# SplitterBoxRevC.net
KiCad netlist of a schematic drawn in EAGLE
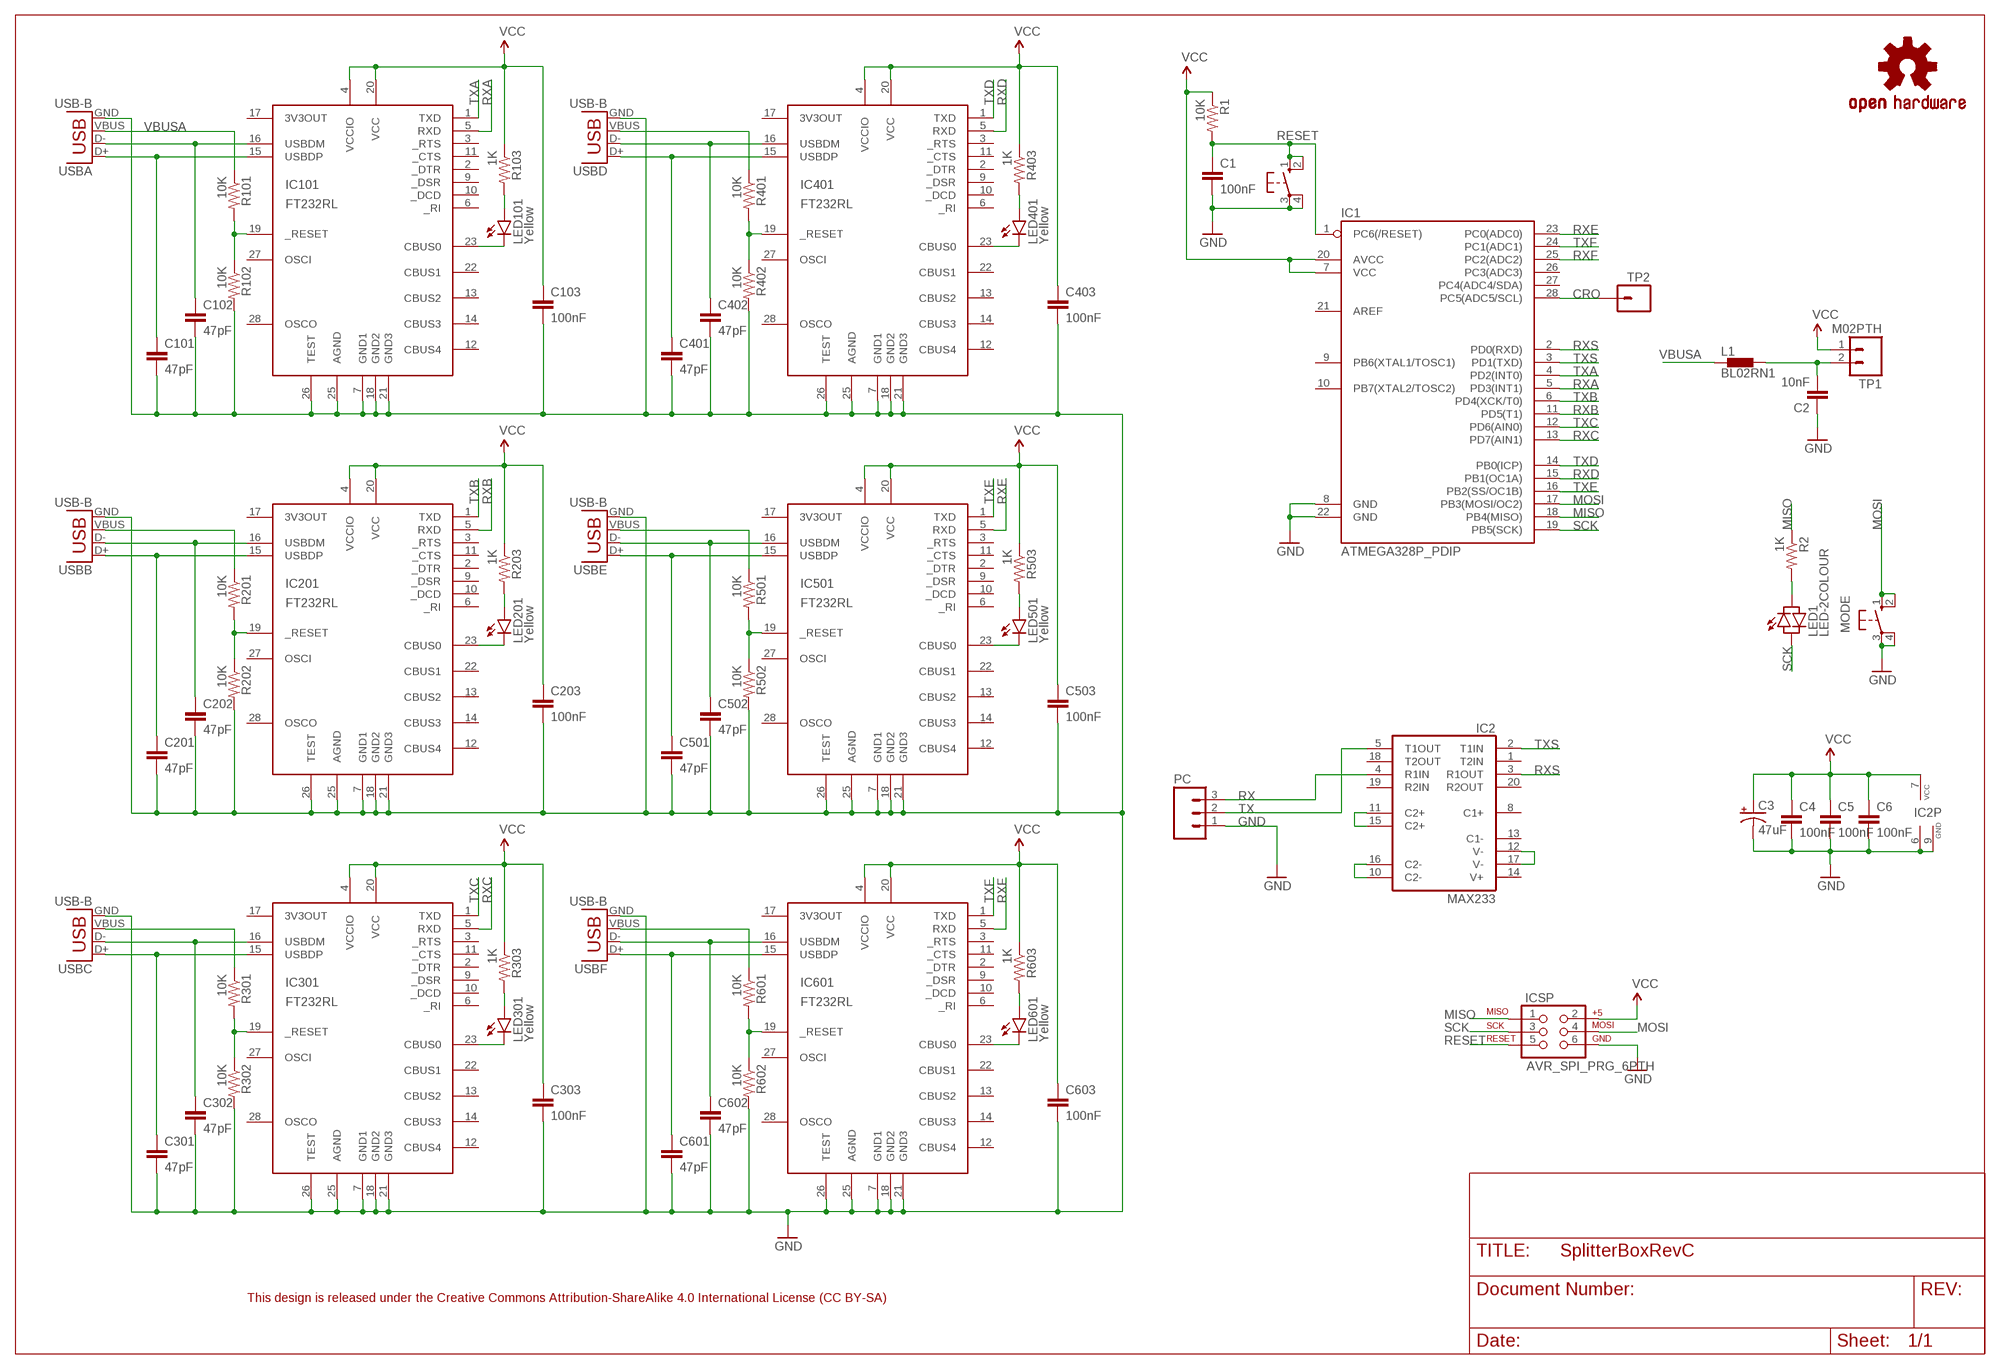
[diagram p0: schematic, sheet 1]

(export (version "E")
  (design (tool "Eeschema 10.0.6"))
  (components
    (comp (ref "C1")
      (value "100nF")
      (footprint "eagle-import:CAP-PTH-SMALL")
      (libsource (lib "eagle-import") (part "CAPPTH"))
    )
    (comp (ref "C2")
      (value "10nF")
      (footprint "eagle-import:CAP-PTH-SMALL")
      (libsource (lib "eagle-import") (part "CAPPTH"))
    )
    (comp (ref "C3")
      (value "47uF")
      (footprint "eagle-import:CPOL-RADIAL-100UF-25V")
      (libsource (lib "eagle-import") (part "CAP_POLPTH1"))
    )
    (comp (ref "C4")
      (value "100nF")
      (footprint "eagle-import:CAP-PTH-SMALL")
      (libsource (lib "eagle-import") (part "CAPPTH"))
    )
    (comp (ref "C5")
      (value "100nF")
      (footprint "eagle-import:CAP-PTH-SMALL")
      (libsource (lib "eagle-import") (part "CAPPTH"))
    )
    (comp (ref "C6")
      (value "100nF")
      (footprint "eagle-import:CAP-PTH-SMALL")
      (libsource (lib "eagle-import") (part "CAPPTH"))
    )
    (comp (ref "C101")
      (value "47pF")
      (footprint "eagle-import:CAP-PTH-SMALL")
      (libsource (lib "eagle-import") (part "CAPPTH"))
    )
    (comp (ref "C102")
      (value "47pF")
      (footprint "eagle-import:CAP-PTH-SMALL")
      (libsource (lib "eagle-import") (part "CAPPTH"))
    )
    (comp (ref "C103")
      (value "100nF")
      (footprint "eagle-import:CAP-PTH-SMALL")
      (libsource (lib "eagle-import") (part "CAPPTH"))
    )
    (comp (ref "C201")
      (value "47pF")
      (footprint "eagle-import:CAP-PTH-SMALL")
      (libsource (lib "eagle-import") (part "CAPPTH"))
    )
    (comp (ref "C202")
      (value "47pF")
      (footprint "eagle-import:CAP-PTH-SMALL")
      (libsource (lib "eagle-import") (part "CAPPTH"))
    )
    (comp (ref "C203")
      (value "100nF")
      (footprint "eagle-import:CAP-PTH-SMALL")
      (libsource (lib "eagle-import") (part "CAPPTH"))
    )
    (comp (ref "C301")
      (value "47pF")
      (footprint "eagle-import:CAP-PTH-SMALL")
      (libsource (lib "eagle-import") (part "CAPPTH"))
    )
    (comp (ref "C302")
      (value "47pF")
      (footprint "eagle-import:CAP-PTH-SMALL")
      (libsource (lib "eagle-import") (part "CAPPTH"))
    )
    (comp (ref "C303")
      (value "100nF")
      (footprint "eagle-import:CAP-PTH-SMALL")
      (libsource (lib "eagle-import") (part "CAPPTH"))
    )
    (comp (ref "C401")
      (value "47pF")
      (footprint "eagle-import:CAP-PTH-SMALL")
      (libsource (lib "eagle-import") (part "CAPPTH"))
    )
    (comp (ref "C402")
      (value "47pF")
      (footprint "eagle-import:CAP-PTH-SMALL")
      (libsource (lib "eagle-import") (part "CAPPTH"))
    )
    (comp (ref "C403")
      (value "100nF")
      (footprint "eagle-import:CAP-PTH-SMALL")
      (libsource (lib "eagle-import") (part "CAPPTH"))
    )
    (comp (ref "C501")
      (value "47pF")
      (footprint "eagle-import:CAP-PTH-SMALL")
      (libsource (lib "eagle-import") (part "CAPPTH"))
    )
    (comp (ref "C502")
      (value "47pF")
      (footprint "eagle-import:CAP-PTH-SMALL")
      (libsource (lib "eagle-import") (part "CAPPTH"))
    )
    (comp (ref "C503")
      (value "100nF")
      (footprint "eagle-import:CAP-PTH-SMALL")
      (libsource (lib "eagle-import") (part "CAPPTH"))
    )
    (comp (ref "C601")
      (value "47pF")
      (footprint "eagle-import:CAP-PTH-SMALL")
      (libsource (lib "eagle-import") (part "CAPPTH"))
    )
    (comp (ref "C602")
      (value "47pF")
      (footprint "eagle-import:CAP-PTH-SMALL")
      (libsource (lib "eagle-import") (part "CAPPTH"))
    )
    (comp (ref "C603")
      (value "100nF")
      (footprint "eagle-import:CAP-PTH-SMALL")
      (libsource (lib "eagle-import") (part "CAPPTH"))
    )
    (comp (ref "IC1")
      (value "ATMEGA328P_PDIP")
      (footprint "eagle-import:DIL28-3")
      (libsource (lib "eagle-import") (part "ATMEGA328P_PDIP"))
    )
    (comp (ref "IC2")
      (value "MAX233")
      (footprint "eagle-import:DIL20")
      (fields (field (name "MPN") "MAX233ACPP+G36"))
      (libsource (lib "eagle-import") (part "MAX233"))
    )
    (comp (ref "IC101")
      (value "FT232RL")
      (footprint "eagle-import:SSOP28DB")
      (libsource (lib "eagle-import") (part "FT232RL"))
    )
    (comp (ref "IC201")
      (value "FT232RL")
      (footprint "eagle-import:SSOP28DB")
      (libsource (lib "eagle-import") (part "FT232RL"))
    )
    (comp (ref "IC301")
      (value "FT232RL")
      (footprint "eagle-import:SSOP28DB")
      (libsource (lib "eagle-import") (part "FT232RL"))
    )
    (comp (ref "IC401")
      (value "FT232RL")
      (footprint "eagle-import:SSOP28DB")
      (libsource (lib "eagle-import") (part "FT232RL"))
    )
    (comp (ref "IC501")
      (value "FT232RL")
      (footprint "eagle-import:SSOP28DB")
      (libsource (lib "eagle-import") (part "FT232RL"))
    )
    (comp (ref "IC601")
      (value "FT232RL")
      (footprint "eagle-import:SSOP28DB")
      (libsource (lib "eagle-import") (part "FT232RL"))
    )
    (comp (ref "ICSP")
      (value "AVR_SPI_PRG_6PTH")
      (footprint "eagle-import:2X3")
      (libsource (lib "eagle-import") (part "AVR_SPI_PRG_6PTH"))
    )
    (comp (ref "L1")
      (value "BL02RN1")
      (footprint "eagle-import:BL02RN1")
      (libsource (lib "eagle-import") (part "BL02RN1"))
    )
    (comp (ref "LED1")
      (value "LED-2COLOUR")
      (footprint "eagle-import:LED3MM")
      (libsource (lib "eagle-import") (part "LED-2COLOUR"))
    )
    (comp (ref "LED101")
      (value "Yellow")
      (footprint "eagle-import:LED3MM_LARGEHOLES")
      (libsource (lib "eagle-import") (part "LED-LH3MM"))
    )
    (comp (ref "LED201")
      (value "Yellow")
      (footprint "eagle-import:LED3MM_LARGEHOLES")
      (libsource (lib "eagle-import") (part "LED-LH3MM"))
    )
    (comp (ref "LED301")
      (value "Yellow")
      (footprint "eagle-import:LED3MM_LARGEHOLES")
      (libsource (lib "eagle-import") (part "LED-LH3MM"))
    )
    (comp (ref "LED401")
      (value "Yellow")
      (footprint "eagle-import:LED3MM_LARGEHOLES")
      (libsource (lib "eagle-import") (part "LED-LH3MM"))
    )
    (comp (ref "LED501")
      (value "Yellow")
      (footprint "eagle-import:LED3MM_LARGEHOLES")
      (libsource (lib "eagle-import") (part "LED-LH3MM"))
    )
    (comp (ref "LED601")
      (value "Yellow")
      (footprint "eagle-import:LED3MM_LARGEHOLES")
      (libsource (lib "eagle-import") (part "LED-LH3MM"))
    )
    (comp (ref "LOGO1")
      (value "OSHW-LOGOS")
      (footprint "eagle-import:OSHW-LOGO-S")
      (libsource (lib "eagle-import") (part "OSHW-LOGOS"))
    )
    (comp (ref "MODE")
      (value "10-XX")
      (footprint "eagle-import:B3F-10XX")
      (fields (field (name "MPN") "B3F-1000"))
      (libsource (lib "eagle-import") (part "10-XX"))
    )
    (comp (ref "PC")
      (value "M03PTH")
      (footprint "eagle-import:1X03")
      (libsource (lib "eagle-import") (part "M03PTH"))
    )
    (comp (ref "R1")
      (value "10K")
      (footprint "eagle-import:AXIAL-0.4")
      (libsource (lib "eagle-import") (part "RESISTORPTH-1/4W"))
    )
    (comp (ref "R2")
      (value "1K")
      (footprint "eagle-import:AXIAL-0.4")
      (libsource (lib "eagle-import") (part "RESISTORPTH-1/4W"))
    )
    (comp (ref "R101")
      (value "10K")
      (footprint "eagle-import:AXIAL-0.4")
      (libsource (lib "eagle-import") (part "RESISTORPTH-1/4W"))
    )
    (comp (ref "R102")
      (value "10K")
      (footprint "eagle-import:AXIAL-0.4")
      (libsource (lib "eagle-import") (part "RESISTORPTH-1/4W"))
    )
    (comp (ref "R103")
      (value "1K")
      (footprint "eagle-import:AXIAL-0.4")
      (libsource (lib "eagle-import") (part "RESISTORPTH-1/4W"))
    )
    (comp (ref "R201")
      (value "10K")
      (footprint "eagle-import:AXIAL-0.4")
      (libsource (lib "eagle-import") (part "RESISTORPTH-1/4W"))
    )
    (comp (ref "R202")
      (value "10K")
      (footprint "eagle-import:AXIAL-0.4")
      (libsource (lib "eagle-import") (part "RESISTORPTH-1/4W"))
    )
    (comp (ref "R203")
      (value "1K")
      (footprint "eagle-import:AXIAL-0.4")
      (libsource (lib "eagle-import") (part "RESISTORPTH-1/4W"))
    )
    (comp (ref "R301")
      (value "10K")
      (footprint "eagle-import:AXIAL-0.4")
      (libsource (lib "eagle-import") (part "RESISTORPTH-1/4W"))
    )
    (comp (ref "R302")
      (value "10K")
      (footprint "eagle-import:AXIAL-0.4")
      (libsource (lib "eagle-import") (part "RESISTORPTH-1/4W"))
    )
    (comp (ref "R303")
      (value "1K")
      (footprint "eagle-import:AXIAL-0.4")
      (libsource (lib "eagle-import") (part "RESISTORPTH-1/4W"))
    )
    (comp (ref "R401")
      (value "10K")
      (footprint "eagle-import:AXIAL-0.4")
      (libsource (lib "eagle-import") (part "RESISTORPTH-1/4W"))
    )
    (comp (ref "R402")
      (value "10K")
      (footprint "eagle-import:AXIAL-0.4")
      (libsource (lib "eagle-import") (part "RESISTORPTH-1/4W"))
    )
    (comp (ref "R403")
      (value "1K")
      (footprint "eagle-import:AXIAL-0.4")
      (libsource (lib "eagle-import") (part "RESISTORPTH-1/4W"))
    )
    (comp (ref "R501")
      (value "10K")
      (footprint "eagle-import:AXIAL-0.4")
      (libsource (lib "eagle-import") (part "RESISTORPTH-1/4W"))
    )
    (comp (ref "R502")
      (value "10K")
      (footprint "eagle-import:AXIAL-0.4")
      (libsource (lib "eagle-import") (part "RESISTORPTH-1/4W"))
    )
    (comp (ref "R503")
      (value "1K")
      (footprint "eagle-import:AXIAL-0.4")
      (libsource (lib "eagle-import") (part "RESISTORPTH-1/4W"))
    )
    (comp (ref "R601")
      (value "10K")
      (footprint "eagle-import:AXIAL-0.4")
      (libsource (lib "eagle-import") (part "RESISTORPTH-1/4W"))
    )
    (comp (ref "R602")
      (value "10K")
      (footprint "eagle-import:AXIAL-0.4")
      (libsource (lib "eagle-import") (part "RESISTORPTH-1/4W"))
    )
    (comp (ref "R603")
      (value "1K")
      (footprint "eagle-import:AXIAL-0.4")
      (libsource (lib "eagle-import") (part "RESISTORPTH-1/4W"))
    )
    (comp (ref "RST")
      (value "10-XX")
      (footprint "eagle-import:B3F-10XX")
      (fields (field (name "MPN") "B3F-1000"))
      (libsource (lib "eagle-import") (part "10-XX"))
    )
    (comp (ref "TP1")
      (value "M02PTH")
      (footprint "eagle-import:1X02")
      (libsource (lib "eagle-import") (part "M02PTH"))
    )
    (comp (ref "TP2")
      (value "M01PTH")
      (footprint "eagle-import:1X01")
      (libsource (lib "eagle-import") (part "M01PTH"))
    )
    (comp (ref "USBA")
      (value "USB-B")
      (footprint "eagle-import:USB-B-PTH")
      (libsource (lib "eagle-import") (part "USBPTH"))
    )
    (comp (ref "USBB")
      (value "USB-B")
      (footprint "eagle-import:USB-B-PTH")
      (libsource (lib "eagle-import") (part "USBPTH"))
    )
    (comp (ref "USBC")
      (value "USB-B")
      (footprint "eagle-import:USB-B-PTH")
      (libsource (lib "eagle-import") (part "USBPTH"))
    )
    (comp (ref "USBD")
      (value "USB-B")
      (footprint "eagle-import:USB-B-PTH")
      (libsource (lib "eagle-import") (part "USBPTH"))
    )
    (comp (ref "USBE")
      (value "USB-B")
      (footprint "eagle-import:USB-B-PTH")
      (libsource (lib "eagle-import") (part "USBPTH"))
    )
    (comp (ref "USBF")
      (value "USB-B")
      (footprint "eagle-import:USB-B-PTH")
      (libsource (lib "eagle-import") (part "USBPTH"))
    )
  )
  (nets
    (net (code "1") (name "/CRO") (class "Default")
      (node (ref "IC1") (pin "28") (pinfunction "PC5(ADC5/SCL)_28") (pintype "bidirectional"))
      (node (ref "TP2") (pin "1") (pinfunction "1_1") (pintype "passive"))
    )
    (net (code "2") (name "/MISO") (class "Default")
      (node (ref "IC1") (pin "18") (pinfunction "PB4(MISO)_18") (pintype "bidirectional"))
      (node (ref "ICSP") (pin "1") (pinfunction "1_1") (pintype "passive"))
      (node (ref "R2") (pin "P$1") (pinfunction "1_P$1") (pintype "passive"))
    )
    (net (code "3") (name "/MOSI") (class "Default")
      (node (ref "IC1") (pin "17") (pinfunction "PB3(MOSI/OC2)_17") (pintype "bidirectional"))
      (node (ref "ICSP") (pin "4") (pinfunction "4_4") (pintype "passive"))
      (node (ref "MODE") (pin "1") (pinfunction "S_1") (pintype "passive"))
      (node (ref "MODE") (pin "2") (pinfunction "S1_2") (pintype "passive"))
    )
    (net (code "4") (name "/RESET") (class "Default")
      (node (ref "C1") (pin "1") (pinfunction "1_1") (pintype "passive"))
      (node (ref "IC1") (pin "1") (pinfunction "PC6(/RESET)_1") (pintype "bidirectional"))
      (node (ref "ICSP") (pin "5") (pinfunction "5_5") (pintype "passive"))
      (node (ref "R1") (pin "P$2") (pinfunction "2_P$2") (pintype "passive"))
      (node (ref "RST") (pin "1") (pinfunction "S_1") (pintype "passive"))
      (node (ref "RST") (pin "2") (pinfunction "S1_2") (pintype "passive"))
    )
    (net (code "5") (name "/RX") (class "Default")
      (node (ref "IC2") (pin "4") (pinfunction "R1IN_4") (pintype "input"))
      (node (ref "PC") (pin "3") (pinfunction "3_3") (pintype "passive"))
    )
    (net (code "6") (name "/RXA") (class "Default")
      (node (ref "IC1") (pin "5") (pinfunction "PD3(INT1)_5") (pintype "bidirectional"))
      (node (ref "IC101") (pin "5") (pinfunction "RXD_5") (pintype "input"))
    )
    (net (code "7") (name "/RXB") (class "Default")
      (node (ref "IC1") (pin "11") (pinfunction "PD5(T1)_11") (pintype "bidirectional"))
      (node (ref "IC201") (pin "5") (pinfunction "RXD_5") (pintype "input"))
    )
    (net (code "8") (name "/RXC") (class "Default")
      (node (ref "IC1") (pin "13") (pinfunction "PD7(AIN1)_13") (pintype "bidirectional"))
      (node (ref "IC301") (pin "5") (pinfunction "RXD_5") (pintype "input"))
    )
    (net (code "9") (name "/RXD") (class "Default")
      (node (ref "IC1") (pin "15") (pinfunction "PB1(OC1A)_15") (pintype "bidirectional"))
      (node (ref "IC401") (pin "5") (pinfunction "RXD_5") (pintype "input"))
    )
    (net (code "10") (name "/RXE") (class "Default")
      (node (ref "IC1") (pin "23") (pinfunction "PC0(ADC0)_23") (pintype "bidirectional"))
      (node (ref "IC501") (pin "5") (pinfunction "RXD_5") (pintype "input"))
    )
    (net (code "11") (name "/RXF") (class "Default")
      (node (ref "IC1") (pin "25") (pinfunction "PC2(ADC2)_25") (pintype "bidirectional"))
      (node (ref "IC601") (pin "5") (pinfunction "RXD_5") (pintype "input"))
    )
    (net (code "12") (name "/RXS") (class "Default")
      (node (ref "IC1") (pin "2") (pinfunction "PD0(RXD)_2") (pintype "bidirectional"))
      (node (ref "IC2") (pin "3") (pinfunction "R1OUT_3") (pintype "output"))
    )
    (net (code "13") (name "/SCK") (class "Default")
      (node (ref "IC1") (pin "19") (pinfunction "PB5(SCK)_19") (pintype "bidirectional"))
      (node (ref "ICSP") (pin "3") (pinfunction "3_3") (pintype "passive"))
      (node (ref "LED1") (pin "K") (pinfunction "C_K") (pintype "passive"))
    )
    (net (code "14") (name "/TX") (class "Default")
      (node (ref "IC2") (pin "5") (pinfunction "T1OUT_5") (pintype "output"))
      (node (ref "PC") (pin "2") (pinfunction "2_2") (pintype "passive"))
    )
    (net (code "15") (name "/TXA") (class "Default")
      (node (ref "IC1") (pin "4") (pinfunction "PD2(INT0)_4") (pintype "bidirectional"))
      (node (ref "IC101") (pin "1") (pinfunction "TXD_1") (pintype "output"))
    )
    (net (code "16") (name "/TXB") (class "Default")
      (node (ref "IC1") (pin "6") (pinfunction "PD4(XCK/T0)_6") (pintype "bidirectional"))
      (node (ref "IC201") (pin "1") (pinfunction "TXD_1") (pintype "output"))
    )
    (net (code "17") (name "/TXC") (class "Default")
      (node (ref "IC1") (pin "12") (pinfunction "PD6(AIN0)_12") (pintype "bidirectional"))
      (node (ref "IC301") (pin "1") (pinfunction "TXD_1") (pintype "output"))
    )
    (net (code "18") (name "/TXD") (class "Default")
      (node (ref "IC1") (pin "14") (pinfunction "PB0(ICP)_14") (pintype "bidirectional"))
      (node (ref "IC401") (pin "1") (pinfunction "TXD_1") (pintype "output"))
    )
    (net (code "19") (name "/TXE") (class "Default")
      (node (ref "IC1") (pin "16") (pinfunction "PB2(SS/OC1B)_16") (pintype "bidirectional"))
      (node (ref "IC501") (pin "1") (pinfunction "TXD_1") (pintype "output"))
    )
    (net (code "20") (name "/TXF") (class "Default")
      (node (ref "IC1") (pin "24") (pinfunction "PC1(ADC1)_24") (pintype "bidirectional"))
      (node (ref "IC601") (pin "1") (pinfunction "TXD_1") (pintype "output"))
    )
    (net (code "21") (name "/TXS") (class "Default")
      (node (ref "IC1") (pin "3") (pinfunction "PD1(TXD)_3") (pintype "bidirectional"))
      (node (ref "IC2") (pin "2") (pinfunction "T1IN_2") (pintype "input"))
    )
    (net (code "22") (name "/VBUSA") (class "Default")
      (node (ref "L1") (pin "1") (pinfunction "1_1") (pintype "passive"))
      (node (ref "R101") (pin "P$1") (pinfunction "1_P$1") (pintype "passive"))
      (node (ref "USBA") (pin "VBUS") (pinfunction "VBUS_VBUS") (pintype "bidirectional"))
    )
    (net (code "23") (name "GND") (class "Default")
      (node (ref "C1") (pin "2") (pinfunction "2_2") (pintype "passive"))
      (node (ref "C101") (pin "2") (pinfunction "2_2") (pintype "passive"))
      (node (ref "C102") (pin "2") (pinfunction "2_2") (pintype "passive"))
      (node (ref "C103") (pin "2") (pinfunction "2_2") (pintype "passive"))
      (node (ref "C2") (pin "1") (pinfunction "1_1") (pintype "passive"))
      (node (ref "C201") (pin "2") (pinfunction "2_2") (pintype "passive"))
      (node (ref "C202") (pin "2") (pinfunction "2_2") (pintype "passive"))
      (node (ref "C203") (pin "2") (pinfunction "2_2") (pintype "passive"))
      (node (ref "C3") (pin "2") (pinfunction "-_2") (pintype "passive"))
      (node (ref "C301") (pin "2") (pinfunction "2_2") (pintype "passive"))
      (node (ref "C302") (pin "2") (pinfunction "2_2") (pintype "passive"))
      (node (ref "C303") (pin "2") (pinfunction "2_2") (pintype "passive"))
      (node (ref "C4") (pin "2") (pinfunction "2_2") (pintype "passive"))
      (node (ref "C401") (pin "2") (pinfunction "2_2") (pintype "passive"))
      (node (ref "C402") (pin "2") (pinfunction "2_2") (pintype "passive"))
      (node (ref "C403") (pin "2") (pinfunction "2_2") (pintype "passive"))
      (node (ref "C5") (pin "2") (pinfunction "2_2") (pintype "passive"))
      (node (ref "C501") (pin "2") (pinfunction "2_2") (pintype "passive"))
      (node (ref "C502") (pin "2") (pinfunction "2_2") (pintype "passive"))
      (node (ref "C503") (pin "2") (pinfunction "2_2") (pintype "passive"))
      (node (ref "C6") (pin "2") (pinfunction "2_2") (pintype "passive"))
      (node (ref "C601") (pin "2") (pinfunction "2_2") (pintype "passive"))
      (node (ref "C602") (pin "2") (pinfunction "2_2") (pintype "passive"))
      (node (ref "C603") (pin "2") (pinfunction "2_2") (pintype "passive"))
      (node (ref "IC1") (pin "22") (pinfunction "GND_22") (pintype "bidirectional"))
      (node (ref "IC1") (pin "8") (pinfunction "GND_8") (pintype "bidirectional"))
      (node (ref "IC101") (pin "18") (pinfunction "GND2_18") (pintype "power_in"))
      (node (ref "IC101") (pin "21") (pinfunction "GND3_21") (pintype "power_in"))
      (node (ref "IC101") (pin "25") (pinfunction "AGND_25") (pintype "power_in"))
      (node (ref "IC101") (pin "26") (pinfunction "TEST_26") (pintype "input"))
      (node (ref "IC101") (pin "7") (pinfunction "GND1_7") (pintype "power_in"))
      (node (ref "IC2") (pin "6") (pinfunction "GND_6") (pintype "power_in"))
      (node (ref "IC2") (pin "9") (pinfunction "GND_9") (pintype "power_in"))
      (node (ref "IC201") (pin "18") (pinfunction "GND2_18") (pintype "power_in"))
      (node (ref "IC201") (pin "21") (pinfunction "GND3_21") (pintype "power_in"))
      (node (ref "IC201") (pin "25") (pinfunction "AGND_25") (pintype "power_in"))
      (node (ref "IC201") (pin "26") (pinfunction "TEST_26") (pintype "input"))
      (node (ref "IC201") (pin "7") (pinfunction "GND1_7") (pintype "power_in"))
      (node (ref "IC301") (pin "18") (pinfunction "GND2_18") (pintype "power_in"))
      (node (ref "IC301") (pin "21") (pinfunction "GND3_21") (pintype "power_in"))
      (node (ref "IC301") (pin "25") (pinfunction "AGND_25") (pintype "power_in"))
      (node (ref "IC301") (pin "26") (pinfunction "TEST_26") (pintype "input"))
      (node (ref "IC301") (pin "7") (pinfunction "GND1_7") (pintype "power_in"))
      (node (ref "IC401") (pin "18") (pinfunction "GND2_18") (pintype "power_in"))
      (node (ref "IC401") (pin "21") (pinfunction "GND3_21") (pintype "power_in"))
      (node (ref "IC401") (pin "25") (pinfunction "AGND_25") (pintype "power_in"))
      (node (ref "IC401") (pin "26") (pinfunction "TEST_26") (pintype "input"))
      (node (ref "IC401") (pin "7") (pinfunction "GND1_7") (pintype "power_in"))
      (node (ref "IC501") (pin "18") (pinfunction "GND2_18") (pintype "power_in"))
      (node (ref "IC501") (pin "21") (pinfunction "GND3_21") (pintype "power_in"))
      (node (ref "IC501") (pin "25") (pinfunction "AGND_25") (pintype "power_in"))
      (node (ref "IC501") (pin "26") (pinfunction "TEST_26") (pintype "input"))
      (node (ref "IC501") (pin "7") (pinfunction "GND1_7") (pintype "power_in"))
      (node (ref "IC601") (pin "18") (pinfunction "GND2_18") (pintype "power_in"))
      (node (ref "IC601") (pin "21") (pinfunction "GND3_21") (pintype "power_in"))
      (node (ref "IC601") (pin "25") (pinfunction "AGND_25") (pintype "power_in"))
      (node (ref "IC601") (pin "26") (pinfunction "TEST_26") (pintype "input"))
      (node (ref "IC601") (pin "7") (pinfunction "GND1_7") (pintype "power_in"))
      (node (ref "ICSP") (pin "6") (pinfunction "6_6") (pintype "passive"))
      (node (ref "MODE") (pin "3") (pinfunction "P_3") (pintype "passive"))
      (node (ref "MODE") (pin "4") (pinfunction "P1_4") (pintype "passive"))
      (node (ref "PC") (pin "1") (pinfunction "1_1") (pintype "passive"))
      (node (ref "R102") (pin "P$2") (pinfunction "2_P$2") (pintype "passive"))
      (node (ref "R202") (pin "P$2") (pinfunction "2_P$2") (pintype "passive"))
      (node (ref "R302") (pin "P$2") (pinfunction "2_P$2") (pintype "passive"))
      (node (ref "R402") (pin "P$2") (pinfunction "2_P$2") (pintype "passive"))
      (node (ref "R502") (pin "P$2") (pinfunction "2_P$2") (pintype "passive"))
      (node (ref "R602") (pin "P$2") (pinfunction "2_P$2") (pintype "passive"))
      (node (ref "RST") (pin "3") (pinfunction "P_3") (pintype "passive"))
      (node (ref "RST") (pin "4") (pinfunction "P1_4") (pintype "passive"))
      (node (ref "USBA") (pin "GND") (pinfunction "GND_GND") (pintype "bidirectional"))
      (node (ref "USBB") (pin "GND") (pinfunction "GND_GND") (pintype "bidirectional"))
      (node (ref "USBC") (pin "GND") (pinfunction "GND_GND") (pintype "bidirectional"))
      (node (ref "USBD") (pin "GND") (pinfunction "GND_GND") (pintype "bidirectional"))
      (node (ref "USBE") (pin "GND") (pinfunction "GND_GND") (pintype "bidirectional"))
      (node (ref "USBF") (pin "GND") (pinfunction "GND_GND") (pintype "bidirectional"))
    )
    (net (code "24") (name "Net-(C2-Pad2)") (class "Default")
      (node (ref "C2") (pin "2") (pinfunction "2_2") (pintype "passive"))
      (node (ref "L1") (pin "2") (pinfunction "2_2") (pintype "passive"))
      (node (ref "TP1") (pin "2") (pinfunction "2_2") (pintype "passive"))
    )
    (net (code "25") (name "Net-(IC2A-C2+-Pad11)") (class "Default")
      (node (ref "IC2") (pin "11") (pinfunction "C2+_11") (pintype "bidirectional"))
      (node (ref "IC2") (pin "15") (pinfunction "C2+_15") (pintype "bidirectional"))
    )
    (net (code "26") (name "Net-(IC2A-C2--Pad10)") (class "Default")
      (node (ref "IC2") (pin "10") (pinfunction "C2-_10") (pintype "bidirectional"))
      (node (ref "IC2") (pin "16") (pinfunction "C2-_16") (pintype "bidirectional"))
    )
    (net (code "27") (name "Net-(IC2A-V--Pad12)") (class "Default")
      (node (ref "IC2") (pin "12") (pinfunction "V-_12") (pintype "bidirectional"))
      (node (ref "IC2") (pin "17") (pinfunction "V-_17") (pintype "bidirectional"))
    )
    (net (code "28") (name "Net-(IC101-CBUS0)") (class "Default")
      (node (ref "IC101") (pin "23") (pinfunction "CBUS0_23") (pintype "bidirectional"))
      (node (ref "LED101") (pin "K") (pinfunction "C_K") (pintype "passive"))
    )
    (net (code "29") (name "Net-(IC101-USBDM)") (class "Default")
      (node (ref "C102") (pin "1") (pinfunction "1_1") (pintype "passive"))
      (node (ref "IC101") (pin "16") (pinfunction "USBDM_16") (pintype "bidirectional"))
      (node (ref "USBA") (pin "D-") (pinfunction "D-_D-") (pintype "bidirectional"))
    )
    (net (code "30") (name "Net-(IC101-USBDP)") (class "Default")
      (node (ref "C101") (pin "1") (pinfunction "1_1") (pintype "passive"))
      (node (ref "IC101") (pin "15") (pinfunction "USBDP_15") (pintype "bidirectional"))
      (node (ref "USBA") (pin "D+") (pinfunction "D+_D+") (pintype "bidirectional"))
    )
    (net (code "31") (name "Net-(IC101-_RESET)") (class "Default")
      (node (ref "IC101") (pin "19") (pinfunction "_RESET_19") (pintype "input"))
      (node (ref "R101") (pin "P$2") (pinfunction "2_P$2") (pintype "passive"))
      (node (ref "R102") (pin "P$1") (pinfunction "1_P$1") (pintype "passive"))
    )
    (net (code "32") (name "Net-(IC201-CBUS0)") (class "Default")
      (node (ref "IC201") (pin "23") (pinfunction "CBUS0_23") (pintype "bidirectional"))
      (node (ref "LED201") (pin "K") (pinfunction "C_K") (pintype "passive"))
    )
    (net (code "33") (name "Net-(IC201-USBDM)") (class "Default")
      (node (ref "C202") (pin "1") (pinfunction "1_1") (pintype "passive"))
      (node (ref "IC201") (pin "16") (pinfunction "USBDM_16") (pintype "bidirectional"))
      (node (ref "USBB") (pin "D-") (pinfunction "D-_D-") (pintype "bidirectional"))
    )
    (net (code "34") (name "Net-(IC201-USBDP)") (class "Default")
      (node (ref "C201") (pin "1") (pinfunction "1_1") (pintype "passive"))
      (node (ref "IC201") (pin "15") (pinfunction "USBDP_15") (pintype "bidirectional"))
      (node (ref "USBB") (pin "D+") (pinfunction "D+_D+") (pintype "bidirectional"))
    )
    (net (code "35") (name "Net-(IC201-_RESET)") (class "Default")
      (node (ref "IC201") (pin "19") (pinfunction "_RESET_19") (pintype "input"))
      (node (ref "R201") (pin "P$2") (pinfunction "2_P$2") (pintype "passive"))
      (node (ref "R202") (pin "P$1") (pinfunction "1_P$1") (pintype "passive"))
    )
    (net (code "36") (name "Net-(IC301-CBUS0)") (class "Default")
      (node (ref "IC301") (pin "23") (pinfunction "CBUS0_23") (pintype "bidirectional"))
      (node (ref "LED301") (pin "K") (pinfunction "C_K") (pintype "passive"))
    )
    (net (code "37") (name "Net-(IC301-USBDM)") (class "Default")
      (node (ref "C302") (pin "1") (pinfunction "1_1") (pintype "passive"))
      (node (ref "IC301") (pin "16") (pinfunction "USBDM_16") (pintype "bidirectional"))
      (node (ref "USBC") (pin "D-") (pinfunction "D-_D-") (pintype "bidirectional"))
    )
    (net (code "38") (name "Net-(IC301-USBDP)") (class "Default")
      (node (ref "C301") (pin "1") (pinfunction "1_1") (pintype "passive"))
      (node (ref "IC301") (pin "15") (pinfunction "USBDP_15") (pintype "bidirectional"))
      (node (ref "USBC") (pin "D+") (pinfunction "D+_D+") (pintype "bidirectional"))
    )
    (net (code "39") (name "Net-(IC301-_RESET)") (class "Default")
      (node (ref "IC301") (pin "19") (pinfunction "_RESET_19") (pintype "input"))
      (node (ref "R301") (pin "P$2") (pinfunction "2_P$2") (pintype "passive"))
      (node (ref "R302") (pin "P$1") (pinfunction "1_P$1") (pintype "passive"))
    )
    (net (code "40") (name "Net-(IC401-CBUS0)") (class "Default")
      (node (ref "IC401") (pin "23") (pinfunction "CBUS0_23") (pintype "bidirectional"))
      (node (ref "LED401") (pin "K") (pinfunction "C_K") (pintype "passive"))
    )
    (net (code "41") (name "Net-(IC401-USBDM)") (class "Default")
      (node (ref "C402") (pin "1") (pinfunction "1_1") (pintype "passive"))
      (node (ref "IC401") (pin "16") (pinfunction "USBDM_16") (pintype "bidirectional"))
      (node (ref "USBD") (pin "D-") (pinfunction "D-_D-") (pintype "bidirectional"))
    )
    (net (code "42") (name "Net-(IC401-USBDP)") (class "Default")
      (node (ref "C401") (pin "1") (pinfunction "1_1") (pintype "passive"))
      (node (ref "IC401") (pin "15") (pinfunction "USBDP_15") (pintype "bidirectional"))
      (node (ref "USBD") (pin "D+") (pinfunction "D+_D+") (pintype "bidirectional"))
    )
    (net (code "43") (name "Net-(IC401-_RESET)") (class "Default")
      (node (ref "IC401") (pin "19") (pinfunction "_RESET_19") (pintype "input"))
      (node (ref "R401") (pin "P$2") (pinfunction "2_P$2") (pintype "passive"))
      (node (ref "R402") (pin "P$1") (pinfunction "1_P$1") (pintype "passive"))
    )
    (net (code "44") (name "Net-(IC501-CBUS0)") (class "Default")
      (node (ref "IC501") (pin "23") (pinfunction "CBUS0_23") (pintype "bidirectional"))
      (node (ref "LED501") (pin "K") (pinfunction "C_K") (pintype "passive"))
    )
    (net (code "45") (name "Net-(IC501-USBDM)") (class "Default")
      (node (ref "C502") (pin "1") (pinfunction "1_1") (pintype "passive"))
      (node (ref "IC501") (pin "16") (pinfunction "USBDM_16") (pintype "bidirectional"))
      (node (ref "USBE") (pin "D-") (pinfunction "D-_D-") (pintype "bidirectional"))
    )
    (net (code "46") (name "Net-(IC501-USBDP)") (class "Default")
      (node (ref "C501") (pin "1") (pinfunction "1_1") (pintype "passive"))
      (node (ref "IC501") (pin "15") (pinfunction "USBDP_15") (pintype "bidirectional"))
      (node (ref "USBE") (pin "D+") (pinfunction "D+_D+") (pintype "bidirectional"))
    )
    (net (code "47") (name "Net-(IC501-_RESET)") (class "Default")
      (node (ref "IC501") (pin "19") (pinfunction "_RESET_19") (pintype "input"))
      (node (ref "R501") (pin "P$2") (pinfunction "2_P$2") (pintype "passive"))
      (node (ref "R502") (pin "P$1") (pinfunction "1_P$1") (pintype "passive"))
    )
    (net (code "48") (name "Net-(IC601-CBUS0)") (class "Default")
      (node (ref "IC601") (pin "23") (pinfunction "CBUS0_23") (pintype "bidirectional"))
      (node (ref "LED601") (pin "K") (pinfunction "C_K") (pintype "passive"))
    )
    (net (code "49") (name "Net-(IC601-USBDM)") (class "Default")
      (node (ref "C602") (pin "1") (pinfunction "1_1") (pintype "passive"))
      (node (ref "IC601") (pin "16") (pinfunction "USBDM_16") (pintype "bidirectional"))
      (node (ref "USBF") (pin "D-") (pinfunction "D-_D-") (pintype "bidirectional"))
    )
    (net (code "50") (name "Net-(IC601-USBDP)") (class "Default")
      (node (ref "C601") (pin "1") (pinfunction "1_1") (pintype "passive"))
      (node (ref "IC601") (pin "15") (pinfunction "USBDP_15") (pintype "bidirectional"))
      (node (ref "USBF") (pin "D+") (pinfunction "D+_D+") (pintype "bidirectional"))
    )
    (net (code "51") (name "Net-(IC601-_RESET)") (class "Default")
      (node (ref "IC601") (pin "19") (pinfunction "_RESET_19") (pintype "input"))
      (node (ref "R601") (pin "P$2") (pinfunction "2_P$2") (pintype "passive"))
      (node (ref "R602") (pin "P$1") (pinfunction "1_P$1") (pintype "passive"))
    )
    (net (code "52") (name "Net-(R2-2)") (class "Default")
      (node (ref "LED1") (pin "A") (pinfunction "A_A") (pintype "passive"))
      (node (ref "R2") (pin "P$2") (pinfunction "2_P$2") (pintype "passive"))
    )
    (net (code "53") (name "Net-(R103-2)") (class "Default")
      (node (ref "LED101") (pin "A") (pinfunction "A_A") (pintype "passive"))
      (node (ref "R103") (pin "P$2") (pinfunction "2_P$2") (pintype "passive"))
    )
    (net (code "54") (name "Net-(R201-1)") (class "Default")
      (node (ref "R201") (pin "P$1") (pinfunction "1_P$1") (pintype "passive"))
      (node (ref "USBB") (pin "VBUS") (pinfunction "VBUS_VBUS") (pintype "bidirectional"))
    )
    (net (code "55") (name "Net-(R203-2)") (class "Default")
      (node (ref "LED201") (pin "A") (pinfunction "A_A") (pintype "passive"))
      (node (ref "R203") (pin "P$2") (pinfunction "2_P$2") (pintype "passive"))
    )
    (net (code "56") (name "Net-(R301-1)") (class "Default")
      (node (ref "R301") (pin "P$1") (pinfunction "1_P$1") (pintype "passive"))
      (node (ref "USBC") (pin "VBUS") (pinfunction "VBUS_VBUS") (pintype "bidirectional"))
    )
    (net (code "57") (name "Net-(R303-2)") (class "Default")
      (node (ref "LED301") (pin "A") (pinfunction "A_A") (pintype "passive"))
      (node (ref "R303") (pin "P$2") (pinfunction "2_P$2") (pintype "passive"))
    )
    (net (code "58") (name "Net-(R401-1)") (class "Default")
      (node (ref "R401") (pin "P$1") (pinfunction "1_P$1") (pintype "passive"))
      (node (ref "USBD") (pin "VBUS") (pinfunction "VBUS_VBUS") (pintype "bidirectional"))
    )
    (net (code "59") (name "Net-(R403-2)") (class "Default")
      (node (ref "LED401") (pin "A") (pinfunction "A_A") (pintype "passive"))
      (node (ref "R403") (pin "P$2") (pinfunction "2_P$2") (pintype "passive"))
    )
    (net (code "60") (name "Net-(R501-1)") (class "Default")
      (node (ref "R501") (pin "P$1") (pinfunction "1_P$1") (pintype "passive"))
      (node (ref "USBE") (pin "VBUS") (pinfunction "VBUS_VBUS") (pintype "bidirectional"))
    )
    (net (code "61") (name "Net-(R503-2)") (class "Default")
      (node (ref "LED501") (pin "A") (pinfunction "A_A") (pintype "passive"))
      (node (ref "R503") (pin "P$2") (pinfunction "2_P$2") (pintype "passive"))
    )
    (net (code "62") (name "Net-(R601-1)") (class "Default")
      (node (ref "R601") (pin "P$1") (pinfunction "1_P$1") (pintype "passive"))
      (node (ref "USBF") (pin "VBUS") (pinfunction "VBUS_VBUS") (pintype "bidirectional"))
    )
    (net (code "63") (name "Net-(R603-2)") (class "Default")
      (node (ref "LED601") (pin "A") (pinfunction "A_A") (pintype "passive"))
      (node (ref "R603") (pin "P$2") (pinfunction "2_P$2") (pintype "passive"))
    )
    (net (code "64") (name "VCC") (class "Default")
      (node (ref "C103") (pin "1") (pinfunction "1_1") (pintype "passive"))
      (node (ref "C203") (pin "1") (pinfunction "1_1") (pintype "passive"))
      (node (ref "C3") (pin "1") (pinfunction "+_1") (pintype "passive"))
      (node (ref "C303") (pin "1") (pinfunction "1_1") (pintype "passive"))
      (node (ref "C4") (pin "1") (pinfunction "1_1") (pintype "passive"))
      (node (ref "C403") (pin "1") (pinfunction "1_1") (pintype "passive"))
      (node (ref "C5") (pin "1") (pinfunction "1_1") (pintype "passive"))
      (node (ref "C503") (pin "1") (pinfunction "1_1") (pintype "passive"))
      (node (ref "C6") (pin "1") (pinfunction "1_1") (pintype "passive"))
      (node (ref "C603") (pin "1") (pinfunction "1_1") (pintype "passive"))
      (node (ref "IC1") (pin "20") (pinfunction "AVCC_20") (pintype "bidirectional"))
      (node (ref "IC1") (pin "7") (pinfunction "VCC_7") (pintype "bidirectional"))
      (node (ref "IC101") (pin "20") (pinfunction "VCC_20") (pintype "power_in"))
      (node (ref "IC101") (pin "4") (pinfunction "VCCIO_4") (pintype "power_in"))
      (node (ref "IC2") (pin "7") (pinfunction "VCC_7") (pintype "power_in"))
      (node (ref "IC201") (pin "20") (pinfunction "VCC_20") (pintype "power_in"))
      (node (ref "IC201") (pin "4") (pinfunction "VCCIO_4") (pintype "power_in"))
      (node (ref "IC301") (pin "20") (pinfunction "VCC_20") (pintype "power_in"))
      (node (ref "IC301") (pin "4") (pinfunction "VCCIO_4") (pintype "power_in"))
      (node (ref "IC401") (pin "20") (pinfunction "VCC_20") (pintype "power_in"))
      (node (ref "IC401") (pin "4") (pinfunction "VCCIO_4") (pintype "power_in"))
      (node (ref "IC501") (pin "20") (pinfunction "VCC_20") (pintype "power_in"))
      (node (ref "IC501") (pin "4") (pinfunction "VCCIO_4") (pintype "power_in"))
      (node (ref "IC601") (pin "20") (pinfunction "VCC_20") (pintype "power_in"))
      (node (ref "IC601") (pin "4") (pinfunction "VCCIO_4") (pintype "power_in"))
      (node (ref "ICSP") (pin "2") (pinfunction "2_2") (pintype "passive"))
      (node (ref "R1") (pin "P$1") (pinfunction "1_P$1") (pintype "passive"))
      (node (ref "R103") (pin "P$1") (pinfunction "1_P$1") (pintype "passive"))
      (node (ref "R203") (pin "P$1") (pinfunction "1_P$1") (pintype "passive"))
      (node (ref "R303") (pin "P$1") (pinfunction "1_P$1") (pintype "passive"))
      (node (ref "R403") (pin "P$1") (pinfunction "1_P$1") (pintype "passive"))
      (node (ref "R503") (pin "P$1") (pinfunction "1_P$1") (pintype "passive"))
      (node (ref "R603") (pin "P$1") (pinfunction "1_P$1") (pintype "passive"))
      (node (ref "TP1") (pin "1") (pinfunction "1_1") (pintype "passive"))
    )
    (net (code "65") (name "unconnected-(IC1-AREF-Pad21)") (class "Default")
      (node (ref "IC1") (pin "21") (pinfunction "AREF_21") (pintype "bidirectional"))
    )
    (net (code "66") (name "unconnected-(IC1-PB6(XTAL1{slash}TOSC1)-Pad9)") (class "Default")
      (node (ref "IC1") (pin "9") (pinfunction "PB6(XTAL1/TOSC1)_9") (pintype "bidirectional"))
    )
    (net (code "67") (name "unconnected-(IC1-PB7(XTAL2{slash}TOSC2)-Pad10)") (class "Default")
      (node (ref "IC1") (pin "10") (pinfunction "PB7(XTAL2/TOSC2)_10") (pintype "bidirectional"))
    )
    (net (code "68") (name "unconnected-(IC1-PC3(ADC3)-Pad26)") (class "Default")
      (node (ref "IC1") (pin "26") (pinfunction "PC3(ADC3)_26") (pintype "bidirectional"))
    )
    (net (code "69") (name "unconnected-(IC1-PC4(ADC4{slash}SDA)-Pad27)") (class "Default")
      (node (ref "IC1") (pin "27") (pinfunction "PC4(ADC4/SDA)_27") (pintype "bidirectional"))
    )
    (net (code "70") (name "unconnected-(IC2A-C1+-Pad8)") (class "Default")
      (node (ref "IC2") (pin "8") (pinfunction "C1+_8") (pintype "bidirectional"))
    )
    (net (code "71") (name "unconnected-(IC2A-C1--Pad13)") (class "Default")
      (node (ref "IC2") (pin "13") (pinfunction "C1-_13") (pintype "bidirectional"))
    )
    (net (code "72") (name "unconnected-(IC2A-R2IN-Pad19)") (class "Default")
      (node (ref "IC2") (pin "19") (pinfunction "R2IN_19") (pintype "input"))
    )
    (net (code "73") (name "unconnected-(IC2A-R2OUT-Pad20)") (class "Default")
      (node (ref "IC2") (pin "20") (pinfunction "R2OUT_20") (pintype "output"))
    )
    (net (code "74") (name "unconnected-(IC2A-T2IN-Pad1)") (class "Default")
      (node (ref "IC2") (pin "1") (pinfunction "T2IN_1") (pintype "input"))
    )
    (net (code "75") (name "unconnected-(IC2A-T2OUT-Pad18)") (class "Default")
      (node (ref "IC2") (pin "18") (pinfunction "T2OUT_18") (pintype "output"))
    )
    (net (code "76") (name "unconnected-(IC2A-V+-Pad14)") (class "Default")
      (node (ref "IC2") (pin "14") (pinfunction "V+_14") (pintype "bidirectional"))
    )
    (net (code "77") (name "unconnected-(IC101-3V3OUT-Pad17)") (class "Default")
      (node (ref "IC101") (pin "17") (pinfunction "3V3OUT_17") (pintype "output"))
    )
    (net (code "78") (name "unconnected-(IC101-CBUS1-Pad22)") (class "Default")
      (node (ref "IC101") (pin "22") (pinfunction "CBUS1_22") (pintype "bidirectional"))
    )
    (net (code "79") (name "unconnected-(IC101-CBUS2-Pad13)") (class "Default")
      (node (ref "IC101") (pin "13") (pinfunction "CBUS2_13") (pintype "bidirectional"))
    )
    (net (code "80") (name "unconnected-(IC101-CBUS3-Pad14)") (class "Default")
      (node (ref "IC101") (pin "14") (pinfunction "CBUS3_14") (pintype "bidirectional"))
    )
    (net (code "81") (name "unconnected-(IC101-CBUS4-Pad12)") (class "Default")
      (node (ref "IC101") (pin "12") (pinfunction "CBUS4_12") (pintype "bidirectional"))
    )
    (net (code "82") (name "unconnected-(IC101-OSCI-Pad27)") (class "Default")
      (node (ref "IC101") (pin "27") (pinfunction "OSCI_27") (pintype "input"))
    )
    (net (code "83") (name "unconnected-(IC101-OSCO-Pad28)") (class "Default")
      (node (ref "IC101") (pin "28") (pinfunction "OSCO_28") (pintype "output"))
    )
    (net (code "84") (name "unconnected-(IC101-_CTS-Pad11)") (class "Default")
      (node (ref "IC101") (pin "11") (pinfunction "_CTS_11") (pintype "input"))
    )
    (net (code "85") (name "unconnected-(IC101-_DCD-Pad10)") (class "Default")
      (node (ref "IC101") (pin "10") (pinfunction "_DCD_10") (pintype "input"))
    )
    (net (code "86") (name "unconnected-(IC101-_DSR-Pad9)") (class "Default")
      (node (ref "IC101") (pin "9") (pinfunction "_DSR_9") (pintype "input"))
    )
    (net (code "87") (name "unconnected-(IC101-_DTR-Pad2)") (class "Default")
      (node (ref "IC101") (pin "2") (pinfunction "_DTR_2") (pintype "output"))
    )
    (net (code "88") (name "unconnected-(IC101-_RI-Pad6)") (class "Default")
      (node (ref "IC101") (pin "6") (pinfunction "_RI_6") (pintype "input"))
    )
    (net (code "89") (name "unconnected-(IC101-_RTS-Pad3)") (class "Default")
      (node (ref "IC101") (pin "3") (pinfunction "_RTS_3") (pintype "output"))
    )
    (net (code "90") (name "unconnected-(IC201-3V3OUT-Pad17)") (class "Default")
      (node (ref "IC201") (pin "17") (pinfunction "3V3OUT_17") (pintype "output"))
    )
    (net (code "91") (name "unconnected-(IC201-CBUS1-Pad22)") (class "Default")
      (node (ref "IC201") (pin "22") (pinfunction "CBUS1_22") (pintype "bidirectional"))
    )
    (net (code "92") (name "unconnected-(IC201-CBUS2-Pad13)") (class "Default")
      (node (ref "IC201") (pin "13") (pinfunction "CBUS2_13") (pintype "bidirectional"))
    )
    (net (code "93") (name "unconnected-(IC201-CBUS3-Pad14)") (class "Default")
      (node (ref "IC201") (pin "14") (pinfunction "CBUS3_14") (pintype "bidirectional"))
    )
    (net (code "94") (name "unconnected-(IC201-CBUS4-Pad12)") (class "Default")
      (node (ref "IC201") (pin "12") (pinfunction "CBUS4_12") (pintype "bidirectional"))
    )
    (net (code "95") (name "unconnected-(IC201-OSCI-Pad27)") (class "Default")
      (node (ref "IC201") (pin "27") (pinfunction "OSCI_27") (pintype "input"))
    )
    (net (code "96") (name "unconnected-(IC201-OSCO-Pad28)") (class "Default")
      (node (ref "IC201") (pin "28") (pinfunction "OSCO_28") (pintype "output"))
    )
    (net (code "97") (name "unconnected-(IC201-_CTS-Pad11)") (class "Default")
      (node (ref "IC201") (pin "11") (pinfunction "_CTS_11") (pintype "input"))
    )
    (net (code "98") (name "unconnected-(IC201-_DCD-Pad10)") (class "Default")
      (node (ref "IC201") (pin "10") (pinfunction "_DCD_10") (pintype "input"))
    )
    (net (code "99") (name "unconnected-(IC201-_DSR-Pad9)") (class "Default")
      (node (ref "IC201") (pin "9") (pinfunction "_DSR_9") (pintype "input"))
    )
    (net (code "100") (name "unconnected-(IC201-_DTR-Pad2)") (class "Default")
      (node (ref "IC201") (pin "2") (pinfunction "_DTR_2") (pintype "output"))
    )
    (net (code "101") (name "unconnected-(IC201-_RI-Pad6)") (class "Default")
      (node (ref "IC201") (pin "6") (pinfunction "_RI_6") (pintype "input"))
    )
    (net (code "102") (name "unconnected-(IC201-_RTS-Pad3)") (class "Default")
      (node (ref "IC201") (pin "3") (pinfunction "_RTS_3") (pintype "output"))
    )
    (net (code "103") (name "unconnected-(IC301-3V3OUT-Pad17)") (class "Default")
      (node (ref "IC301") (pin "17") (pinfunction "3V3OUT_17") (pintype "output"))
    )
    (net (code "104") (name "unconnected-(IC301-CBUS1-Pad22)") (class "Default")
      (node (ref "IC301") (pin "22") (pinfunction "CBUS1_22") (pintype "bidirectional"))
    )
    (net (code "105") (name "unconnected-(IC301-CBUS2-Pad13)") (class "Default")
      (node (ref "IC301") (pin "13") (pinfunction "CBUS2_13") (pintype "bidirectional"))
    )
    (net (code "106") (name "unconnected-(IC301-CBUS3-Pad14)") (class "Default")
      (node (ref "IC301") (pin "14") (pinfunction "CBUS3_14") (pintype "bidirectional"))
    )
    (net (code "107") (name "unconnected-(IC301-CBUS4-Pad12)") (class "Default")
      (node (ref "IC301") (pin "12") (pinfunction "CBUS4_12") (pintype "bidirectional"))
    )
    (net (code "108") (name "unconnected-(IC301-OSCI-Pad27)") (class "Default")
      (node (ref "IC301") (pin "27") (pinfunction "OSCI_27") (pintype "input"))
    )
    (net (code "109") (name "unconnected-(IC301-OSCO-Pad28)") (class "Default")
      (node (ref "IC301") (pin "28") (pinfunction "OSCO_28") (pintype "output"))
    )
    (net (code "110") (name "unconnected-(IC301-_CTS-Pad11)") (class "Default")
      (node (ref "IC301") (pin "11") (pinfunction "_CTS_11") (pintype "input"))
    )
    (net (code "111") (name "unconnected-(IC301-_DCD-Pad10)") (class "Default")
      (node (ref "IC301") (pin "10") (pinfunction "_DCD_10") (pintype "input"))
    )
    (net (code "112") (name "unconnected-(IC301-_DSR-Pad9)") (class "Default")
      (node (ref "IC301") (pin "9") (pinfunction "_DSR_9") (pintype "input"))
    )
    (net (code "113") (name "unconnected-(IC301-_DTR-Pad2)") (class "Default")
      (node (ref "IC301") (pin "2") (pinfunction "_DTR_2") (pintype "output"))
    )
    (net (code "114") (name "unconnected-(IC301-_RI-Pad6)") (class "Default")
      (node (ref "IC301") (pin "6") (pinfunction "_RI_6") (pintype "input"))
    )
    (net (code "115") (name "unconnected-(IC301-_RTS-Pad3)") (class "Default")
      (node (ref "IC301") (pin "3") (pinfunction "_RTS_3") (pintype "output"))
    )
    (net (code "116") (name "unconnected-(IC401-3V3OUT-Pad17)") (class "Default")
      (node (ref "IC401") (pin "17") (pinfunction "3V3OUT_17") (pintype "output"))
    )
    (net (code "117") (name "unconnected-(IC401-CBUS1-Pad22)") (class "Default")
      (node (ref "IC401") (pin "22") (pinfunction "CBUS1_22") (pintype "bidirectional"))
    )
    (net (code "118") (name "unconnected-(IC401-CBUS2-Pad13)") (class "Default")
      (node (ref "IC401") (pin "13") (pinfunction "CBUS2_13") (pintype "bidirectional"))
    )
    (net (code "119") (name "unconnected-(IC401-CBUS3-Pad14)") (class "Default")
      (node (ref "IC401") (pin "14") (pinfunction "CBUS3_14") (pintype "bidirectional"))
    )
    (net (code "120") (name "unconnected-(IC401-CBUS4-Pad12)") (class "Default")
      (node (ref "IC401") (pin "12") (pinfunction "CBUS4_12") (pintype "bidirectional"))
    )
    (net (code "121") (name "unconnected-(IC401-OSCI-Pad27)") (class "Default")
      (node (ref "IC401") (pin "27") (pinfunction "OSCI_27") (pintype "input"))
    )
    (net (code "122") (name "unconnected-(IC401-OSCO-Pad28)") (class "Default")
      (node (ref "IC401") (pin "28") (pinfunction "OSCO_28") (pintype "output"))
    )
    (net (code "123") (name "unconnected-(IC401-_CTS-Pad11)") (class "Default")
      (node (ref "IC401") (pin "11") (pinfunction "_CTS_11") (pintype "input"))
    )
    (net (code "124") (name "unconnected-(IC401-_DCD-Pad10)") (class "Default")
      (node (ref "IC401") (pin "10") (pinfunction "_DCD_10") (pintype "input"))
    )
    (net (code "125") (name "unconnected-(IC401-_DSR-Pad9)") (class "Default")
      (node (ref "IC401") (pin "9") (pinfunction "_DSR_9") (pintype "input"))
    )
    (net (code "126") (name "unconnected-(IC401-_DTR-Pad2)") (class "Default")
      (node (ref "IC401") (pin "2") (pinfunction "_DTR_2") (pintype "output"))
    )
    (net (code "127") (name "unconnected-(IC401-_RI-Pad6)") (class "Default")
      (node (ref "IC401") (pin "6") (pinfunction "_RI_6") (pintype "input"))
    )
    (net (code "128") (name "unconnected-(IC401-_RTS-Pad3)") (class "Default")
      (node (ref "IC401") (pin "3") (pinfunction "_RTS_3") (pintype "output"))
    )
    (net (code "129") (name "unconnected-(IC501-3V3OUT-Pad17)") (class "Default")
      (node (ref "IC501") (pin "17") (pinfunction "3V3OUT_17") (pintype "output"))
    )
    (net (code "130") (name "unconnected-(IC501-CBUS1-Pad22)") (class "Default")
      (node (ref "IC501") (pin "22") (pinfunction "CBUS1_22") (pintype "bidirectional"))
    )
    (net (code "131") (name "unconnected-(IC501-CBUS2-Pad13)") (class "Default")
      (node (ref "IC501") (pin "13") (pinfunction "CBUS2_13") (pintype "bidirectional"))
    )
    (net (code "132") (name "unconnected-(IC501-CBUS3-Pad14)") (class "Default")
      (node (ref "IC501") (pin "14") (pinfunction "CBUS3_14") (pintype "bidirectional"))
    )
    (net (code "133") (name "unconnected-(IC501-CBUS4-Pad12)") (class "Default")
      (node (ref "IC501") (pin "12") (pinfunction "CBUS4_12") (pintype "bidirectional"))
    )
    (net (code "134") (name "unconnected-(IC501-OSCI-Pad27)") (class "Default")
      (node (ref "IC501") (pin "27") (pinfunction "OSCI_27") (pintype "input"))
    )
    (net (code "135") (name "unconnected-(IC501-OSCO-Pad28)") (class "Default")
      (node (ref "IC501") (pin "28") (pinfunction "OSCO_28") (pintype "output"))
    )
    (net (code "136") (name "unconnected-(IC501-_CTS-Pad11)") (class "Default")
      (node (ref "IC501") (pin "11") (pinfunction "_CTS_11") (pintype "input"))
    )
    (net (code "137") (name "unconnected-(IC501-_DCD-Pad10)") (class "Default")
      (node (ref "IC501") (pin "10") (pinfunction "_DCD_10") (pintype "input"))
    )
    (net (code "138") (name "unconnected-(IC501-_DSR-Pad9)") (class "Default")
      (node (ref "IC501") (pin "9") (pinfunction "_DSR_9") (pintype "input"))
    )
    (net (code "139") (name "unconnected-(IC501-_DTR-Pad2)") (class "Default")
      (node (ref "IC501") (pin "2") (pinfunction "_DTR_2") (pintype "output"))
    )
    (net (code "140") (name "unconnected-(IC501-_RI-Pad6)") (class "Default")
      (node (ref "IC501") (pin "6") (pinfunction "_RI_6") (pintype "input"))
    )
    (net (code "141") (name "unconnected-(IC501-_RTS-Pad3)") (class "Default")
      (node (ref "IC501") (pin "3") (pinfunction "_RTS_3") (pintype "output"))
    )
    (net (code "142") (name "unconnected-(IC601-3V3OUT-Pad17)") (class "Default")
      (node (ref "IC601") (pin "17") (pinfunction "3V3OUT_17") (pintype "output"))
    )
    (net (code "143") (name "unconnected-(IC601-CBUS1-Pad22)") (class "Default")
      (node (ref "IC601") (pin "22") (pinfunction "CBUS1_22") (pintype "bidirectional"))
    )
    (net (code "144") (name "unconnected-(IC601-CBUS2-Pad13)") (class "Default")
      (node (ref "IC601") (pin "13") (pinfunction "CBUS2_13") (pintype "bidirectional"))
    )
    (net (code "145") (name "unconnected-(IC601-CBUS3-Pad14)") (class "Default")
      (node (ref "IC601") (pin "14") (pinfunction "CBUS3_14") (pintype "bidirectional"))
    )
    (net (code "146") (name "unconnected-(IC601-CBUS4-Pad12)") (class "Default")
      (node (ref "IC601") (pin "12") (pinfunction "CBUS4_12") (pintype "bidirectional"))
    )
    (net (code "147") (name "unconnected-(IC601-OSCI-Pad27)") (class "Default")
      (node (ref "IC601") (pin "27") (pinfunction "OSCI_27") (pintype "input"))
    )
    (net (code "148") (name "unconnected-(IC601-OSCO-Pad28)") (class "Default")
      (node (ref "IC601") (pin "28") (pinfunction "OSCO_28") (pintype "output"))
    )
    (net (code "149") (name "unconnected-(IC601-_CTS-Pad11)") (class "Default")
      (node (ref "IC601") (pin "11") (pinfunction "_CTS_11") (pintype "input"))
    )
    (net (code "150") (name "unconnected-(IC601-_DCD-Pad10)") (class "Default")
      (node (ref "IC601") (pin "10") (pinfunction "_DCD_10") (pintype "input"))
    )
    (net (code "151") (name "unconnected-(IC601-_DSR-Pad9)") (class "Default")
      (node (ref "IC601") (pin "9") (pinfunction "_DSR_9") (pintype "input"))
    )
    (net (code "152") (name "unconnected-(IC601-_DTR-Pad2)") (class "Default")
      (node (ref "IC601") (pin "2") (pinfunction "_DTR_2") (pintype "output"))
    )
    (net (code "153") (name "unconnected-(IC601-_RI-Pad6)") (class "Default")
      (node (ref "IC601") (pin "6") (pinfunction "_RI_6") (pintype "input"))
    )
    (net (code "154") (name "unconnected-(IC601-_RTS-Pad3)") (class "Default")
      (node (ref "IC601") (pin "3") (pinfunction "_RTS_3") (pintype "output"))
    )
  )
)
